# talking-train.net
KiCad netlist of a schematic drawn in EasyEDA Pro
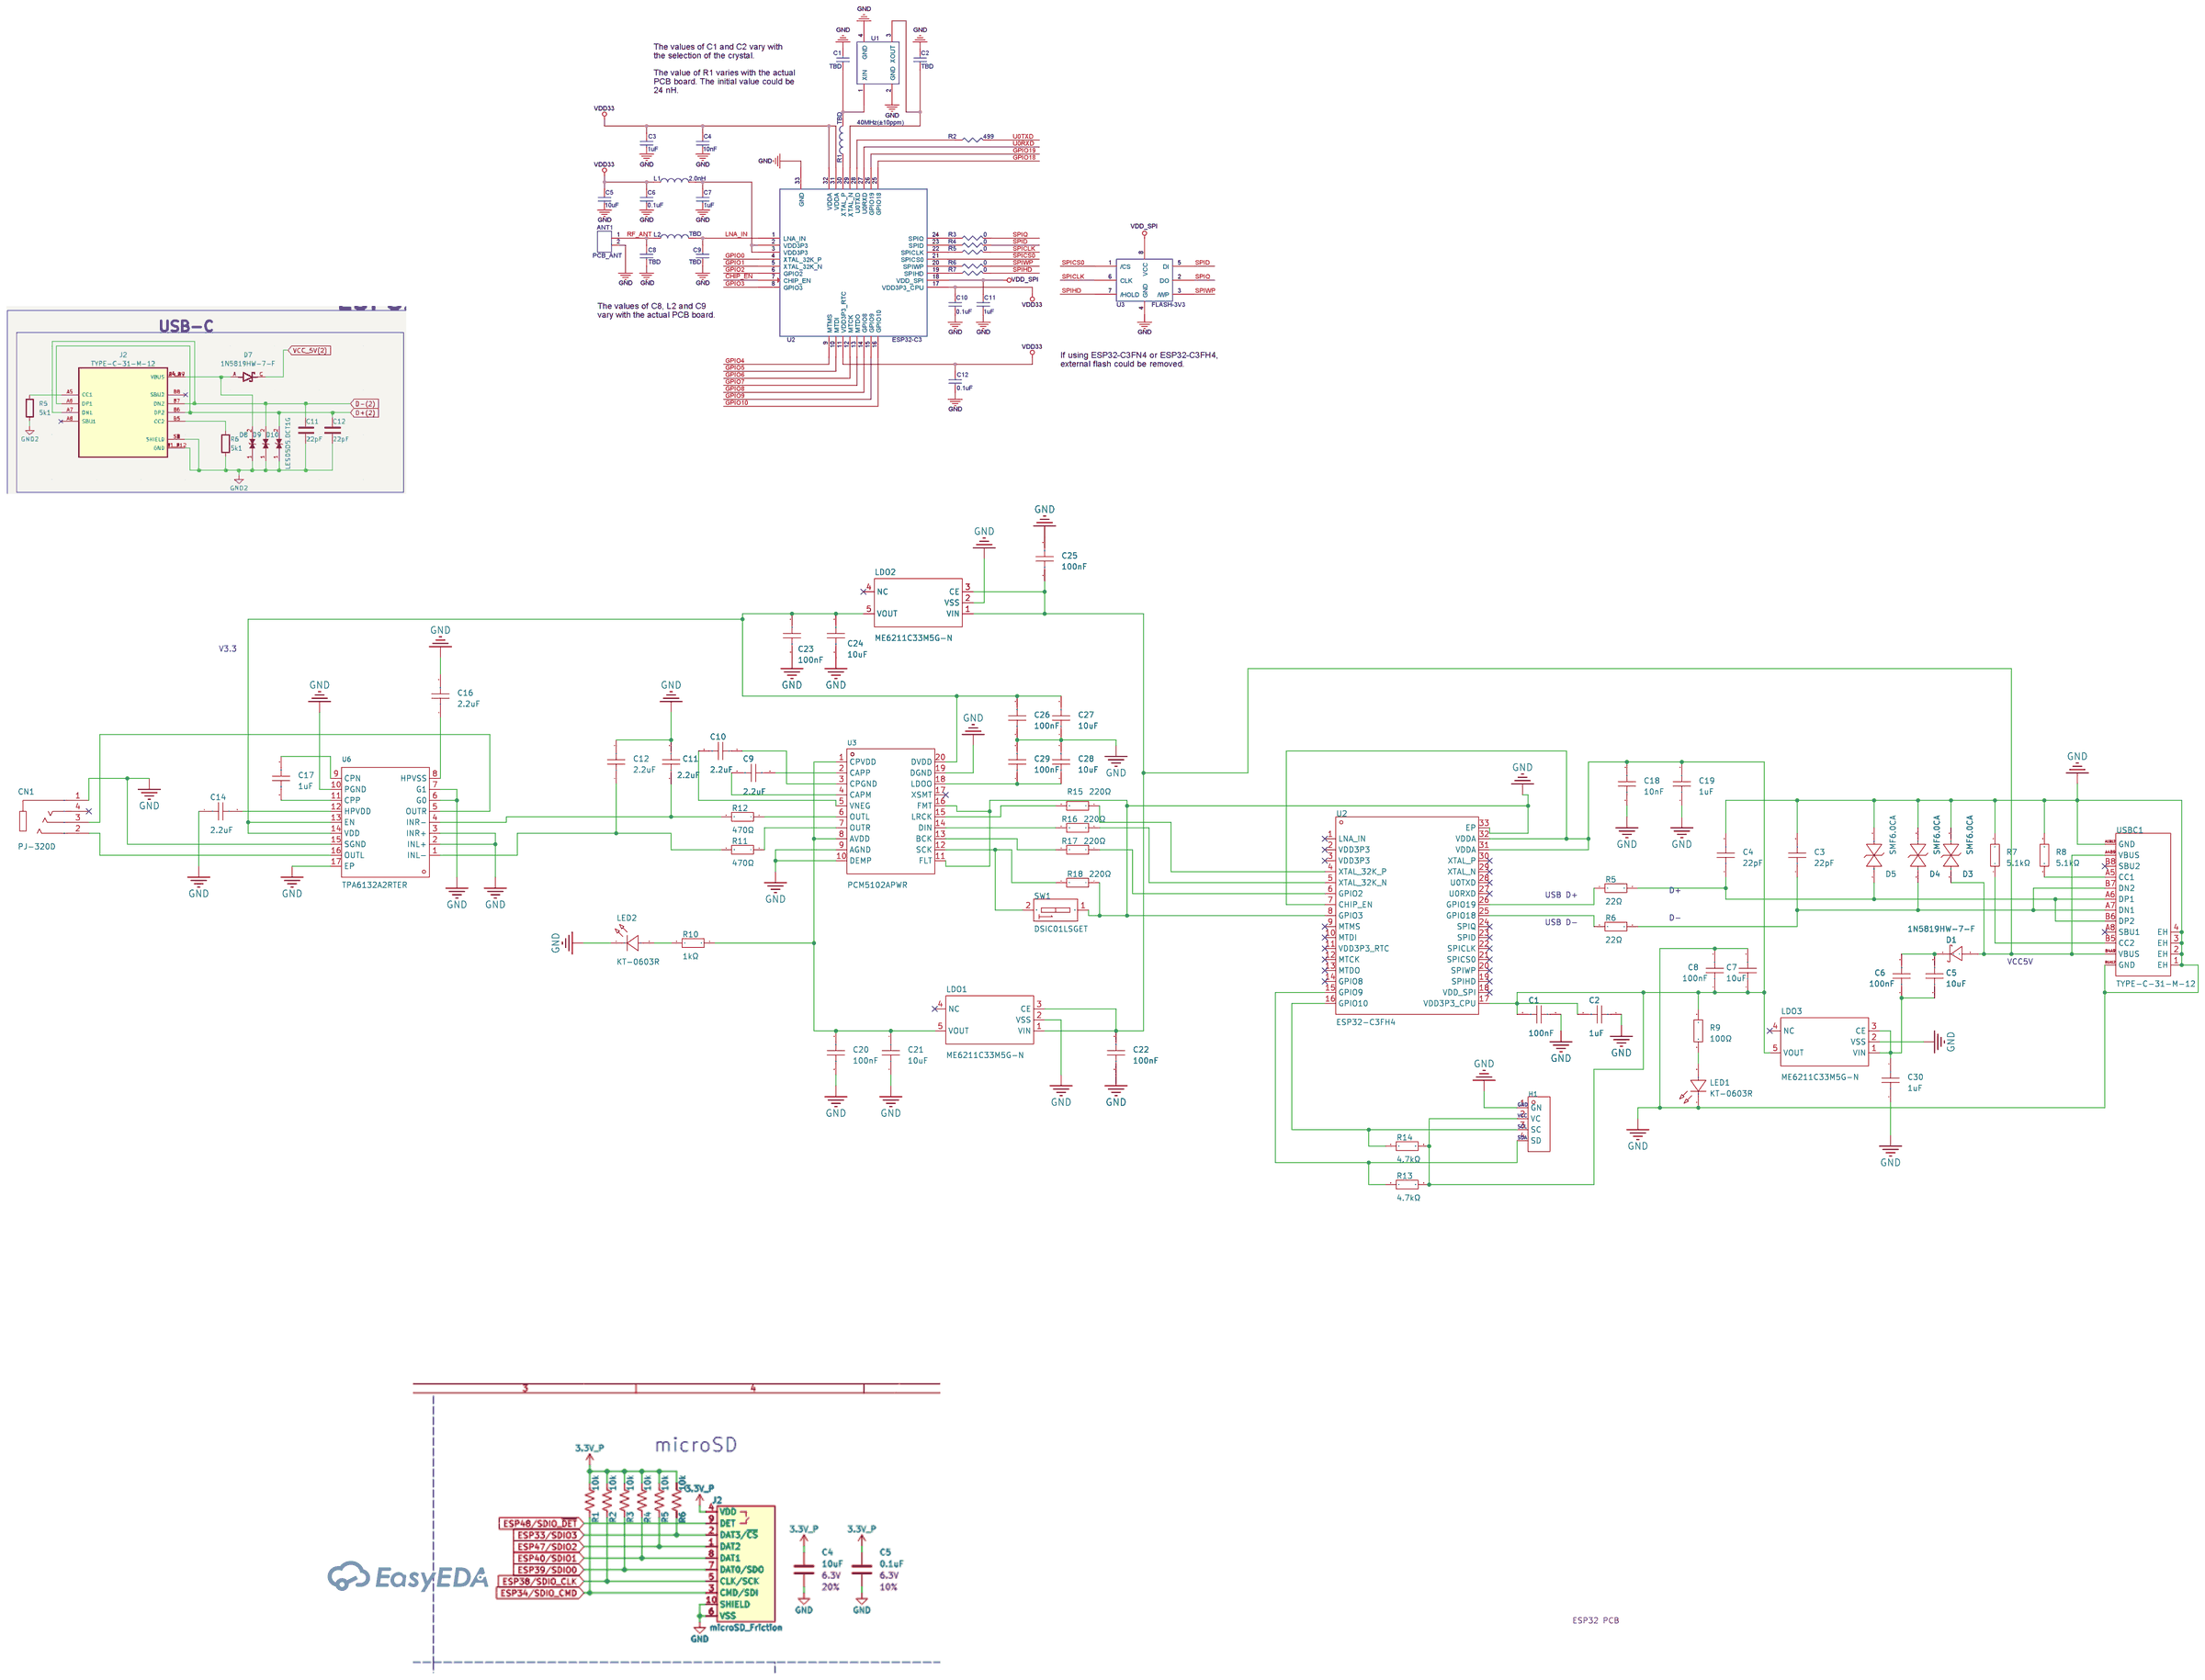
[diagram p0: schematic sheet]

(export (version "E")
  (design (tool "Eeschema 10.0.6"))
  (components
    (comp (ref "C1")
      (value "100nF")
      (footprint "easyedapro:C0603")
      (description "Capacitance:100nF Tolerance:±10% Tolerance:±10% Voltage Rating:50V Temperature Coefficient:X7R")
      (fields
        (field (name "Manufacturer Part") "CC0603KRX7R9BB104")
        (field (name "Manufacturer") "YAGEO(国巨)")
      )
      (libsource (lib "easyedapro") (part "CAP"))
    )
    (comp (ref "C2")
      (value "1uF")
      (footprint "easyedapro:C0603")
      (description "Capacitance:1uF Tolerance:±10% Tolerance:±10% Voltage Rating:50V Temperature Coefficient:X5R")
      (fields
        (field (name "Manufacturer Part") "CL10A105KB8NNNC")
        (field (name "Manufacturer") "SAMSUNG(三星)")
      )
      (libsource (lib "easyedapro") (part "CAP"))
    )
    (comp (ref "C3")
      (value "22pF")
      (footprint "easyedapro:C0603")
      (description "Capacitance:22pF Tolerance:±5% Tolerance:±5% Voltage Rating:50V Temperature Coefficient:C0G")
      (fields
        (field (name "Manufacturer Part") "CL10C220JB8NNNC")
        (field (name "Manufacturer") "SAMSUNG(三星)")
      )
      (libsource (lib "easyedapro") (part "CAP"))
    )
    (comp (ref "C4")
      (value "22pF")
      (footprint "easyedapro:C0603")
      (description "Capacitance:22pF Tolerance:±5% Tolerance:±5% Voltage Rating:50V Temperature Coefficient:C0G")
      (fields
        (field (name "Manufacturer Part") "CL10C220JB8NNNC")
        (field (name "Manufacturer") "SAMSUNG(三星)")
      )
      (libsource (lib "easyedapro") (part "CAP"))
    )
    (comp (ref "C5")
      (value "10uF")
      (footprint "easyedapro:C0603")
      (description "Capacitance:10uF Tolerance:±10% Tolerance:±10% Voltage Rating:10V Temperature Coefficient:X5R")
      (fields
        (field (name "Manufacturer Part") "CL10A106KP8NNNC")
        (field (name "Manufacturer") "SAMSUNG(三星)")
      )
      (libsource (lib "easyedapro") (part "CAP"))
    )
    (comp (ref "C6")
      (value "100nF")
      (footprint "easyedapro:C0603")
      (description "Capacitance:100nF Tolerance:±10% Tolerance:±10% Voltage Rating:50V Temperature Coefficient:X7R")
      (fields
        (field (name "Manufacturer Part") "CC0603KRX7R9BB104")
        (field (name "Manufacturer") "YAGEO(国巨)")
      )
      (libsource (lib "easyedapro") (part "CAP"))
    )
    (comp (ref "C7")
      (value "10uF")
      (footprint "easyedapro:C0603")
      (description "Capacitance:10uF Tolerance:±10% Tolerance:±10% Voltage Rating:10V Temperature Coefficient:X5R")
      (fields
        (field (name "Manufacturer Part") "CL10A106KP8NNNC")
        (field (name "Manufacturer") "SAMSUNG(三星)")
      )
      (libsource (lib "easyedapro") (part "CAP"))
    )
    (comp (ref "C8")
      (value "100nF")
      (footprint "easyedapro:C0603")
      (description "Capacitance:100nF Tolerance:±10% Tolerance:±10% Voltage Rating:50V Temperature Coefficient:X7R")
      (fields
        (field (name "Manufacturer Part") "CC0603KRX7R9BB104")
        (field (name "Manufacturer") "YAGEO(国巨)")
      )
      (libsource (lib "easyedapro") (part "CAP"))
    )
    (comp (ref "C9")
      (value "2.2uF")
      (footprint "easyedapro:C0603")
      (description "Capacitance:2.2uF Tolerance:±10% Tolerance:±10% Voltage Rating:16V Temperature Coefficient:X5R")
      (fields
        (field (name "Manufacturer Part") "CL10A225KO8NNNC")
        (field (name "Manufacturer") "SAMSUNG(三星)")
      )
      (libsource (lib "easyedapro") (part "CAP"))
    )
    (comp (ref "C10")
      (value "2.2uF")
      (footprint "easyedapro:C0603")
      (description "Capacitance:2.2uF Tolerance:±10% Tolerance:±10% Voltage Rating:16V Temperature Coefficient:X5R")
      (fields
        (field (name "Manufacturer Part") "CL10A225KO8NNNC")
        (field (name "Manufacturer") "SAMSUNG(三星)")
      )
      (libsource (lib "easyedapro") (part "CAP"))
    )
    (comp (ref "C11")
      (value "2.2uF")
      (footprint "easyedapro:C0603")
      (description "Capacitance:2.2uF Tolerance:±10% Tolerance:±10% Voltage Rating:16V Temperature Coefficient:X5R")
      (fields
        (field (name "Manufacturer Part") "CL10A225KO8NNNC")
        (field (name "Manufacturer") "SAMSUNG(三星)")
      )
      (libsource (lib "easyedapro") (part "CAP"))
    )
    (comp (ref "C12")
      (value "2.2uF")
      (footprint "easyedapro:C0603")
      (description "Capacitance:2.2uF Tolerance:±10% Tolerance:±10% Voltage Rating:16V Temperature Coefficient:X5R")
      (fields
        (field (name "Manufacturer Part") "CL10A225KO8NNNC")
        (field (name "Manufacturer") "SAMSUNG(三星)")
      )
      (libsource (lib "easyedapro") (part "CAP"))
    )
    (comp (ref "C14")
      (value "2.2uF")
      (footprint "easyedapro:C0603")
      (description "Capacitance:2.2uF Tolerance:±10% Tolerance:±10% Voltage Rating:16V Temperature Coefficient:X5R")
      (fields
        (field (name "Manufacturer Part") "CL10A225KO8NNNC")
        (field (name "Manufacturer") "SAMSUNG(三星)")
      )
      (libsource (lib "easyedapro") (part "CAP"))
    )
    (comp (ref "C16")
      (value "2.2uF")
      (footprint "easyedapro:C0603")
      (description "Capacitance:2.2uF Tolerance:±10% Tolerance:±10% Voltage Rating:16V Temperature Coefficient:X5R")
      (fields
        (field (name "Manufacturer Part") "CL10A225KO8NNNC")
        (field (name "Manufacturer") "SAMSUNG(三星)")
      )
      (libsource (lib "easyedapro") (part "CAP"))
    )
    (comp (ref "C17")
      (value "1uF")
      (footprint "easyedapro:C0603")
      (description "Capacitance:1uF Tolerance:±10% Tolerance:±10% Voltage Rating:50V Temperature Coefficient:X5R")
      (fields
        (field (name "Manufacturer Part") "CL10A105KB8NNNC")
        (field (name "Manufacturer") "SAMSUNG(三星)")
      )
      (libsource (lib "easyedapro") (part "CAP"))
    )
    (comp (ref "C18")
      (value "10nF")
      (footprint "easyedapro:C0603")
      (description "Capacitance:10nF Tolerance:±10% Tolerance:±10% Voltage Rating:50V Temperature Coefficient:X7R")
      (fields (field (name "Manufacturer Part") "0603B103K500NT") (field (name "Manufacturer") "FH(风华)"))
      (libsource (lib "easyedapro") (part "CAP"))
    )
    (comp (ref "C19")
      (value "1uF")
      (footprint "easyedapro:C0603")
      (description "Capacitance:1uF Tolerance:±10% Tolerance:±10% Voltage Rating:50V Temperature Coefficient:X5R")
      (fields
        (field (name "Manufacturer Part") "CL10A105KB8NNNC")
        (field (name "Manufacturer") "SAMSUNG(三星)")
      )
      (libsource (lib "easyedapro") (part "CAP"))
    )
    (comp (ref "C20")
      (value "100nF")
      (footprint "easyedapro:C0603")
      (description "Capacitance:100nF Tolerance:±10% Tolerance:±10% Voltage Rating:50V Temperature Coefficient:X7R")
      (fields
        (field (name "Manufacturer Part") "CC0603KRX7R9BB104")
        (field (name "Manufacturer") "YAGEO(国巨)")
      )
      (libsource (lib "easyedapro") (part "CAP"))
    )
    (comp (ref "C21")
      (value "10uF")
      (footprint "easyedapro:C0603")
      (description "Capacitance:10uF Tolerance:±10% Tolerance:±10% Voltage Rating:10V Temperature Coefficient:X5R")
      (fields
        (field (name "Manufacturer Part") "CL10A106KP8NNNC")
        (field (name "Manufacturer") "SAMSUNG(三星)")
      )
      (libsource (lib "easyedapro") (part "CAP"))
    )
    (comp (ref "C22")
      (value "100nF")
      (footprint "easyedapro:C0603")
      (description "Capacitance:100nF Tolerance:±10% Tolerance:±10% Voltage Rating:50V Temperature Coefficient:X7R")
      (fields
        (field (name "Manufacturer Part") "CC0603KRX7R9BB104")
        (field (name "Manufacturer") "YAGEO(国巨)")
      )
      (libsource (lib "easyedapro") (part "CAP"))
    )
    (comp (ref "C23")
      (value "100nF")
      (footprint "easyedapro:C0603")
      (description "Capacitance:100nF Tolerance:±10% Tolerance:±10% Voltage Rating:50V Temperature Coefficient:X7R")
      (fields
        (field (name "Manufacturer Part") "CC0603KRX7R9BB104")
        (field (name "Manufacturer") "YAGEO(国巨)")
      )
      (libsource (lib "easyedapro") (part "CAP"))
    )
    (comp (ref "C24")
      (value "10uF")
      (footprint "easyedapro:C0603")
      (description "Capacitance:10uF Tolerance:±10% Tolerance:±10% Voltage Rating:10V Temperature Coefficient:X5R")
      (fields
        (field (name "Manufacturer Part") "CL10A106KP8NNNC")
        (field (name "Manufacturer") "SAMSUNG(三星)")
      )
      (libsource (lib "easyedapro") (part "CAP"))
    )
    (comp (ref "C25")
      (value "100nF")
      (footprint "easyedapro:C0603")
      (description "Capacitance:100nF Tolerance:±10% Tolerance:±10% Voltage Rating:50V Temperature Coefficient:X7R")
      (fields
        (field (name "Manufacturer Part") "CC0603KRX7R9BB104")
        (field (name "Manufacturer") "YAGEO(国巨)")
      )
      (libsource (lib "easyedapro") (part "CAP"))
    )
    (comp (ref "C26")
      (value "100nF")
      (footprint "easyedapro:C0603")
      (description "Capacitance:100nF Tolerance:±10% Tolerance:±10% Voltage Rating:50V Temperature Coefficient:X7R")
      (fields
        (field (name "Manufacturer Part") "CC0603KRX7R9BB104")
        (field (name "Manufacturer") "YAGEO(国巨)")
      )
      (libsource (lib "easyedapro") (part "CAP"))
    )
    (comp (ref "C27")
      (value "10uF")
      (footprint "easyedapro:C0603")
      (description "Capacitance:10uF Tolerance:±10% Tolerance:±10% Voltage Rating:10V Temperature Coefficient:X5R")
      (fields
        (field (name "Manufacturer Part") "CL10A106KP8NNNC")
        (field (name "Manufacturer") "SAMSUNG(三星)")
      )
      (libsource (lib "easyedapro") (part "CAP"))
    )
    (comp (ref "C28")
      (value "10uF")
      (footprint "easyedapro:C0603")
      (description "Capacitance:10uF Tolerance:±10% Tolerance:±10% Voltage Rating:10V Temperature Coefficient:X5R")
      (fields
        (field (name "Manufacturer Part") "CL10A106KP8NNNC")
        (field (name "Manufacturer") "SAMSUNG(三星)")
      )
      (libsource (lib "easyedapro") (part "CAP"))
    )
    (comp (ref "C29")
      (value "100nF")
      (footprint "easyedapro:C0603")
      (description "Capacitance:100nF Tolerance:±10% Tolerance:±10% Voltage Rating:50V Temperature Coefficient:X7R")
      (fields
        (field (name "Manufacturer Part") "CC0603KRX7R9BB104")
        (field (name "Manufacturer") "YAGEO(国巨)")
      )
      (libsource (lib "easyedapro") (part "CAP"))
    )
    (comp (ref "C30")
      (value "1uF")
      (footprint "easyedapro:C0603")
      (description "Capacitance:1uF Tolerance:±10% Tolerance:±10% Voltage Rating:50V Temperature Coefficient:X7R")
      (fields
        (field (name "Manufacturer Part") "CL31B105KBHNNNE")
        (field (name "Manufacturer") "SAMSUNG(三星)")
      )
      (libsource (lib "easyedapro") (part "CAP"))
    )
    (comp (ref "CN1")
      (value "PJ-320D")
      (footprint "easyedapro:AUDIO-SMD_PJ-320D-1")
      (fields (field (name "Manufacturer") "SHOU HAN(首韩)"))
      (libsource (lib "easyedapro") (part "PJ-320D"))
    )
    (comp (ref "D1")
      (value "1N5819HW-7-F")
      (footprint "easyedapro:SOD-123_L2.7-W1.6-LS3.7-RD")
      (fields (field (name "Manufacturer") "DIODES(美台)"))
      (libsource (lib "easyedapro") (part "1N5819HW-7-F"))
    )
    (comp (ref "D3")
      (value "SMF6.0CA")
      (footprint "easyedapro:SOD-123FL_L2.7-W1.8-LS3.8-BI")
      (fields (field (name "Manufacturer") "R+O(宏嘉诚)"))
      (libsource (lib "easyedapro") (part "SMF6.0CA_C19077500"))
    )
    (comp (ref "D4")
      (value "SMF6.0CA")
      (footprint "easyedapro:SOD-123FL_L2.7-W1.8-LS3.8-BI")
      (fields (field (name "Manufacturer") "R+O(宏嘉诚)"))
      (libsource (lib "easyedapro") (part "SMF6.0CA_C19077500"))
    )
    (comp (ref "D5")
      (value "SMF6.0CA")
      (footprint "easyedapro:SOD-123FL_L2.7-W1.8-LS3.8-BI")
      (fields (field (name "Manufacturer") "R+O(宏嘉诚)"))
      (libsource (lib "easyedapro") (part "SMF6.0CA_C19077500"))
    )
    (comp (ref "H1")
      (value "2.54-1*4P母")
      (footprint "easyedapro:HDR-TH_4P-P2.54-V-F")
      (fields (field (name "Manufacturer") "BOOMELE(博穆精密)"))
      (libsource (lib "easyedapro") (part "2.54-1*4P母"))
    )
    (comp (ref "LDO1")
      (value "ME6211C33M5G-N")
      (footprint "easyedapro:SOT-23-5_L3.0-W1.7-P0.95-LS2.8-BL")
      (fields (field (name "Manufacturer") "MICRONE(南京微盟)"))
      (libsource (lib "easyedapro") (part "ME6211C33M5G-N"))
    )
    (comp (ref "LDO2")
      (value "ME6211C33M5G-N")
      (footprint "easyedapro:SOT-23-5_L3.0-W1.7-P0.95-LS2.8-BL")
      (fields (field (name "Manufacturer") "MICRONE(南京微盟)"))
      (libsource (lib "easyedapro") (part "ME6211C33M5G-N"))
    )
    (comp (ref "LDO3")
      (value "ME6211C33M5G-N")
      (footprint "easyedapro:SOT-23-5_L3.0-W1.7-P0.95-LS2.8-BL")
      (fields (field (name "Manufacturer") "MICRONE(南京微盟)"))
      (libsource (lib "easyedapro") (part "ME6211C33M5G-N"))
    )
    (comp (ref "LED1")
      (value "KT-0603R")
      (footprint "easyedapro:LED0603-RD_RED")
      (fields (field (name "Manufacturer") "KENTO"))
      (libsource (lib "easyedapro") (part "XL-1608SURC-06"))
    )
    (comp (ref "LED2")
      (value "KT-0603R")
      (footprint "easyedapro:LED0603-RD_RED")
      (fields (field (name "Manufacturer") "KENTO"))
      (libsource (lib "easyedapro") (part "XL-1608SURC-06"))
    )
    (comp (ref "R5")
      (value "22Ω")
      (footprint "easyedapro:R0603")
      (fields
        (field (name "Manufacturer Part") "0603WAF220JT5E")
        (field (name "Manufacturer") "UNI-ROYAL(厚声)")
      )
      (libsource (lib "easyedapro") (part "Res"))
    )
    (comp (ref "R6")
      (value "22Ω")
      (footprint "easyedapro:R0603")
      (fields
        (field (name "Manufacturer Part") "0603WAF220JT5E")
        (field (name "Manufacturer") "UNI-ROYAL(厚声)")
      )
      (libsource (lib "easyedapro") (part "Res"))
    )
    (comp (ref "R7")
      (value "5.1kΩ")
      (footprint "easyedapro:R0603")
      (fields
        (field (name "Manufacturer Part") "0805W8F5101T5E")
        (field (name "Manufacturer") "UNI-ROYAL(厚声)")
      )
      (libsource (lib "easyedapro") (part "Res"))
    )
    (comp (ref "R8")
      (value "5.1kΩ")
      (footprint "easyedapro:R0603")
      (fields
        (field (name "Manufacturer Part") "0805W8F5101T5E")
        (field (name "Manufacturer") "UNI-ROYAL(厚声)")
      )
      (libsource (lib "easyedapro") (part "Res"))
    )
    (comp (ref "R9")
      (value "100Ω")
      (footprint "easyedapro:R0603")
      (fields
        (field (name "Manufacturer Part") "0603WAF1000T5E")
        (field (name "Manufacturer") "UNI-ROYAL(厚声)")
      )
      (libsource (lib "easyedapro") (part "Res"))
    )
    (comp (ref "R10")
      (value "1kΩ")
      (footprint "easyedapro:R0603")
      (fields
        (field (name "Manufacturer Part") "0603WAF1001T5E")
        (field (name "Manufacturer") "UNI-ROYAL(厚声)")
      )
      (libsource (lib "easyedapro") (part "Res"))
    )
    (comp (ref "R11")
      (value "470Ω")
      (footprint "easyedapro:R0603")
      (fields
        (field (name "Manufacturer Part") "0603WAF4700T5E")
        (field (name "Manufacturer") "UNI-ROYAL(厚声)")
      )
      (libsource (lib "easyedapro") (part "Res"))
    )
    (comp (ref "R12")
      (value "470Ω")
      (footprint "easyedapro:R0603")
      (fields
        (field (name "Manufacturer Part") "0603WAF4700T5E")
        (field (name "Manufacturer") "UNI-ROYAL(厚声)")
      )
      (libsource (lib "easyedapro") (part "Res"))
    )
    (comp (ref "R13")
      (value "4.7kΩ")
      (footprint "easyedapro:R0603")
      (fields
        (field (name "Manufacturer Part") "0603WAF4701T5E")
        (field (name "Manufacturer") "UNI-ROYAL(厚声)")
      )
      (libsource (lib "easyedapro") (part "Res"))
    )
    (comp (ref "R14")
      (value "4.7kΩ")
      (footprint "easyedapro:R0603")
      (fields
        (field (name "Manufacturer Part") "0603WAF4701T5E")
        (field (name "Manufacturer") "UNI-ROYAL(厚声)")
      )
      (libsource (lib "easyedapro") (part "Res"))
    )
    (comp (ref "R15")
      (value "220Ω")
      (footprint "easyedapro:R0603")
      (fields
        (field (name "Manufacturer Part") "0603WAF2200T5E")
        (field (name "Manufacturer") "UNI-ROYAL(厚声)")
      )
      (libsource (lib "easyedapro") (part "Res"))
    )
    (comp (ref "R16")
      (value "220Ω")
      (footprint "easyedapro:R0603")
      (fields
        (field (name "Manufacturer Part") "0603WAF2200T5E")
        (field (name "Manufacturer") "UNI-ROYAL(厚声)")
      )
      (libsource (lib "easyedapro") (part "Res"))
    )
    (comp (ref "R17")
      (value "220Ω")
      (footprint "easyedapro:R0603")
      (fields
        (field (name "Manufacturer Part") "0603WAF2200T5E")
        (field (name "Manufacturer") "UNI-ROYAL(厚声)")
      )
      (libsource (lib "easyedapro") (part "Res"))
    )
    (comp (ref "R18")
      (value "220Ω")
      (footprint "easyedapro:R0603")
      (fields
        (field (name "Manufacturer Part") "0603WAF2200T5E")
        (field (name "Manufacturer") "UNI-ROYAL(厚声)")
      )
      (libsource (lib "easyedapro") (part "Res"))
    )
    (comp (ref "SW1")
      (value "DSIC01LSGET")
      (footprint "easyedapro:SW-SMD_DSIC01LSGET")
      (description "Type:Slide, Rocked Circuit:SPST Number of Positions:1 Lead Pitch:- Operating Life:- Color:Black")
      (fields (field (name "Manufacturer") "YE"))
      (libsource (lib "easyedapro") (part "DSIC01LSGET"))
    )
    (comp (ref "U2")
      (value "ESP32-C3FH4")
      (footprint "easyedapro:QFN-32_L5.0-W5.0-P0.50-TL-EP3.7")
      (fields (field (name "Manufacturer") "ESPRESSIF(乐鑫)"))
      (libsource (lib "easyedapro") (part "ESP32-C3FH4"))
    )
    (comp (ref "U3")
      (value "PCM5102APWR")
      (footprint "easyedapro:TSSOP-20_L6.5-W4.4-P0.65-LS6.4-BL")
      (fields (field (name "Manufacturer") "TI(德州仪器)"))
      (libsource (lib "easyedapro") (part "PCM5102APWR"))
    )
    (comp (ref "U6")
      (value "TPA6132A2RTER")
      (footprint "easyedapro:WQFN-16_L3.0-W3.0-P0.50-TL-EP1.6")
      (fields (field (name "Manufacturer") "TI(德州仪器)"))
      (libsource (lib "easyedapro") (part "TPA6132A2RTER"))
    )
    (comp (ref "USBC1")
      (value "TYPE-C-31-M-12")
      (footprint "easyedapro:USB-C_SMD-TYPE-C-31-M-12_1")
      (fields (field (name "Manufacturer") "韩国韩荣"))
      (libsource (lib "easyedapro") (part "TYPE-C-31-M-12"))
    )
  )
  (nets
    (net (code "1") (name "GND") (class "Default")
      (node (ref "C1") (pin "1") (pinfunction "1_1") (pintype "input"))
      (node (ref "C11") (pin "2") (pinfunction "2_2") (pintype "input"))
      (node (ref "C12") (pin "2") (pinfunction "2_2") (pintype "input"))
      (node (ref "C14") (pin "1") (pinfunction "1_1") (pintype "input"))
      (node (ref "C16") (pin "2") (pinfunction "2_2") (pintype "input"))
      (node (ref "C18") (pin "1") (pinfunction "1_1") (pintype "input"))
      (node (ref "C19") (pin "1") (pinfunction "1_1") (pintype "input"))
      (node (ref "C2") (pin "1") (pinfunction "1_1") (pintype "input"))
      (node (ref "C20") (pin "2") (pinfunction "2_2") (pintype "input"))
      (node (ref "C21") (pin "2") (pinfunction "2_2") (pintype "input"))
      (node (ref "C22") (pin "2") (pinfunction "2_2") (pintype "input"))
      (node (ref "C23") (pin "2") (pinfunction "2_2") (pintype "input"))
      (node (ref "C24") (pin "2") (pinfunction "2_2") (pintype "input"))
      (node (ref "C25") (pin "2") (pinfunction "2_2") (pintype "input"))
      (node (ref "C26") (pin "1") (pinfunction "1_1") (pintype "input"))
      (node (ref "C27") (pin "1") (pinfunction "1_1") (pintype "input"))
      (node (ref "C28") (pin "2") (pinfunction "2_2") (pintype "input"))
      (node (ref "C29") (pin "2") (pinfunction "2_2") (pintype "input"))
      (node (ref "C3") (pin "2") (pinfunction "2_2") (pintype "input"))
      (node (ref "C30") (pin "2") (pinfunction "2_2") (pintype "input"))
      (node (ref "C4") (pin "2") (pinfunction "2_2") (pintype "input"))
      (node (ref "C7") (pin "2") (pinfunction "2_2") (pintype "input"))
      (node (ref "C8") (pin "2") (pinfunction "2_2") (pintype "input"))
      (node (ref "CN1") (pin "1") (pinfunction "1_1") (pintype "unspecified"))
      (node (ref "D3") (pin "1") (pinfunction "1_1") (pintype "unspecified"))
      (node (ref "D4") (pin "1") (pinfunction "1_1") (pintype "unspecified"))
      (node (ref "D5") (pin "1") (pinfunction "1_1") (pintype "unspecified"))
      (node (ref "H1") (pin "1") (pinfunction "GN_1") (pintype "input"))
      (node (ref "LDO1") (pin "2") (pinfunction "VSS_2") (pintype "unspecified"))
      (node (ref "LDO2") (pin "2") (pinfunction "VSS_2") (pintype "unspecified"))
      (node (ref "LDO3") (pin "2") (pinfunction "VSS_2") (pintype "unspecified"))
      (node (ref "LED1") (pin "1") (pinfunction "K_1") (pintype "unspecified"))
      (node (ref "LED2") (pin "1") (pinfunction "K_1") (pintype "unspecified"))
      (node (ref "R18") (pin "1") (pinfunction "1_1") (pintype "input"))
      (node (ref "R7") (pin "2") (pinfunction "2_2") (pintype "input"))
      (node (ref "R8") (pin "2") (pinfunction "2_2") (pintype "input"))
      (node (ref "SW1") (pin "1") (pinfunction "A1_1") (pintype "input"))
      (node (ref "U2") (pin "33") (pinfunction "EP_33") (pintype "unspecified"))
      (node (ref "U2") (pin "8") (pinfunction "GPIO3_8") (pintype "unspecified"))
      (node (ref "U3") (pin "10") (pinfunction "DEMP_10") (pintype "input"))
      (node (ref "U3") (pin "11") (pinfunction "FLT_11") (pintype "input"))
      (node (ref "U3") (pin "16") (pinfunction "FMT_16") (pintype "input"))
      (node (ref "U3") (pin "19") (pinfunction "DGND_19") (pintype "input"))
      (node (ref "U3") (pin "9") (pinfunction "AGND_9") (pintype "input"))
      (node (ref "U6") (pin "10") (pinfunction "PGND_10") (pintype "input"))
      (node (ref "U6") (pin "15") (pinfunction "SGND_15") (pintype "input"))
      (node (ref "U6") (pin "17") (pinfunction "EP_17") (pintype "input"))
      (node (ref "U6") (pin "2") (pinfunction "INL+_2") (pintype "input"))
      (node (ref "U6") (pin "3") (pinfunction "INR+_3") (pintype "input"))
      (node (ref "U6") (pin "6") (pinfunction "G0_6") (pintype "input"))
      (node (ref "U6") (pin "7") (pinfunction "G1_7") (pintype "input"))
      (node (ref "USBC1") (pin "1") (pinfunction "EH_1") (pintype "unspecified"))
      (node (ref "USBC1") (pin "2") (pinfunction "EH_2") (pintype "unspecified"))
      (node (ref "USBC1") (pin "3") (pinfunction "EH_3") (pintype "unspecified"))
      (node (ref "USBC1") (pin "4") (pinfunction "EH_4") (pintype "unspecified"))
      (node (ref "USBC1") (pin "A1B12") (pinfunction "GND_A1B12") (pintype "unspecified"))
      (node (ref "USBC1") (pin "B1A12") (pinfunction "GND_B1A12") (pintype "unspecified"))
    )
    (net (code "2") (name "Net-(D1-A)") (class "Default")
      (node (ref "C22") (pin "1") (pinfunction "1_1") (pintype "input"))
      (node (ref "C25") (pin "1") (pinfunction "1_1") (pintype "input"))
      (node (ref "D1") (pin "2") (pinfunction "A_2") (pintype "unspecified"))
      (node (ref "D3") (pin "2") (pinfunction "2_2") (pintype "unspecified"))
      (node (ref "LDO1") (pin "1") (pinfunction "VIN_1") (pintype "unspecified"))
      (node (ref "LDO1") (pin "3") (pinfunction "CE_3") (pintype "unspecified"))
      (node (ref "LDO2") (pin "1") (pinfunction "VIN_1") (pintype "unspecified"))
      (node (ref "LDO2") (pin "3") (pinfunction "CE_3") (pintype "unspecified"))
      (node (ref "USBC1") (pin "A4B9") (pinfunction "VBUS_A4B9") (pintype "unspecified"))
      (node (ref "USBC1") (pin "B4A9") (pinfunction "VBUS_B4A9") (pintype "unspecified"))
    )
    (net (code "3") (name "Net-(D1-K)") (class "Default")
      (node (ref "C5") (pin "2") (pinfunction "2_2") (pintype "input"))
      (node (ref "C6") (pin "2") (pinfunction "2_2") (pintype "input"))
      (node (ref "D1") (pin "1") (pinfunction "K_1") (pintype "unspecified"))
    )
    (net (code "4") (name "Net-(H1-SC)") (class "Default")
      (node (ref "H1") (pin "3") (pinfunction "SC_3") (pintype "input"))
      (node (ref "R14") (pin "1") (pinfunction "1_1") (pintype "input"))
      (node (ref "U2") (pin "16") (pinfunction "GPIO10_16") (pintype "unspecified"))
    )
    (net (code "5") (name "Net-(H1-SD)") (class "Default")
      (node (ref "H1") (pin "4") (pinfunction "SD_4") (pintype "input"))
      (node (ref "R13") (pin "1") (pinfunction "1_1") (pintype "input"))
      (node (ref "U2") (pin "15") (pinfunction "GPIO9_15") (pintype "unspecified"))
    )
    (net (code "6") (name "Net-(H1-VC)") (class "Default")
      (node (ref "C1") (pin "2") (pinfunction "2_2") (pintype "input"))
      (node (ref "C18") (pin "2") (pinfunction "2_2") (pintype "input"))
      (node (ref "C19") (pin "2") (pinfunction "2_2") (pintype "input"))
      (node (ref "C2") (pin "2") (pinfunction "2_2") (pintype "input"))
      (node (ref "C7") (pin "1") (pinfunction "1_1") (pintype "input"))
      (node (ref "C8") (pin "1") (pinfunction "1_1") (pintype "input"))
      (node (ref "H1") (pin "2") (pinfunction "VC_2") (pintype "input"))
      (node (ref "LDO3") (pin "5") (pinfunction "VOUT_5") (pintype "unspecified"))
      (node (ref "R13") (pin "2") (pinfunction "2_2") (pintype "input"))
      (node (ref "R14") (pin "2") (pinfunction "2_2") (pintype "input"))
      (node (ref "R9") (pin "2") (pinfunction "2_2") (pintype "input"))
      (node (ref "U2") (pin "17") (pinfunction "VDD3P3_CPU_17") (pintype "unspecified"))
      (node (ref "U2") (pin "31") (pinfunction "VDDA_31") (pintype "unspecified"))
      (node (ref "U2") (pin "32") (pinfunction "VDDA_32") (pintype "unspecified"))
      (node (ref "U2") (pin "7") (pinfunction "CHIP_EN_7") (pintype "unspecified"))
    )
    (net (code "7") (name "Net-(LDO1-VOUT)") (class "Default")
      (node (ref "C20") (pin "1") (pinfunction "1_1") (pintype "input"))
      (node (ref "C21") (pin "1") (pinfunction "1_1") (pintype "input"))
      (node (ref "LDO1") (pin "5") (pinfunction "VOUT_5") (pintype "unspecified"))
      (node (ref "R10") (pin "1") (pinfunction "1_1") (pintype "input"))
      (node (ref "U3") (pin "1") (pinfunction "CPVDD_1") (pintype "input"))
      (node (ref "U3") (pin "8") (pinfunction "AVDD_8") (pintype "input"))
    )
    (net (code "8") (name "Net-(LDO2-VOUT)") (class "Default")
      (node (ref "C23") (pin "1") (pinfunction "1_1") (pintype "input"))
      (node (ref "C24") (pin "1") (pinfunction "1_1") (pintype "input"))
      (node (ref "C26") (pin "2") (pinfunction "2_2") (pintype "input"))
      (node (ref "C27") (pin "2") (pinfunction "2_2") (pintype "input"))
      (node (ref "LDO2") (pin "5") (pinfunction "VOUT_5") (pintype "unspecified"))
      (node (ref "U3") (pin "20") (pinfunction "DVDD_20") (pintype "input"))
      (node (ref "U6") (pin "13") (pinfunction "EN_13") (pintype "input"))
      (node (ref "U6") (pin "14") (pinfunction "VDD_14") (pintype "input"))
    )
    (net (code "9") (name "Net-(LDO3-CE)") (class "Default")
      (node (ref "C30") (pin "1") (pinfunction "1_1") (pintype "input"))
      (node (ref "C5") (pin "1") (pinfunction "1_1") (pintype "input"))
      (node (ref "C6") (pin "1") (pinfunction "1_1") (pintype "input"))
      (node (ref "LDO3") (pin "1") (pinfunction "VIN_1") (pintype "unspecified"))
      (node (ref "LDO3") (pin "3") (pinfunction "CE_3") (pintype "unspecified"))
    )
    (net (code "10") (name "Net-(LED1-A)") (class "Default")
      (node (ref "LED1") (pin "2") (pinfunction "A_2") (pintype "unspecified"))
      (node (ref "R9") (pin "1") (pinfunction "1_1") (pintype "input"))
    )
    (net (code "11") (name "Net-(LED2-A)") (class "Default")
      (node (ref "LED2") (pin "2") (pinfunction "A_2") (pintype "unspecified"))
      (node (ref "R10") (pin "2") (pinfunction "2_2") (pintype "input"))
    )
    (net (code "12") (name "Net-(SW1-A2)") (class "Default")
      (node (ref "R18") (pin "2") (pinfunction "2_2") (pintype "input"))
      (node (ref "SW1") (pin "2") (pinfunction "A2_2") (pintype "input"))
      (node (ref "U3") (pin "12") (pinfunction "SCK_12") (pintype "input"))
    )
    (net (code "13") (name "Net-(U2-GPIO2)") (class "Default")
      (node (ref "R17") (pin "1") (pinfunction "1_1") (pintype "input"))
      (node (ref "U2") (pin "6") (pinfunction "GPIO2_6") (pintype "unspecified"))
    )
    (net (code "14") (name "Net-(U2-GPIO18)") (class "Default")
      (node (ref "R6") (pin "1") (pinfunction "1_1") (pintype "input"))
      (node (ref "U2") (pin "25") (pinfunction "GPIO18_25") (pintype "unspecified"))
    )
    (net (code "15") (name "Net-(U2-GPIO19)") (class "Default")
      (node (ref "R5") (pin "1") (pinfunction "1_1") (pintype "input"))
      (node (ref "U2") (pin "26") (pinfunction "GPIO19_26") (pintype "unspecified"))
    )
    (net (code "16") (name "Net-(U2-XTAL_32K_N)") (class "Default")
      (node (ref "R16") (pin "1") (pinfunction "1_1") (pintype "input"))
      (node (ref "U2") (pin "5") (pinfunction "XTAL_32K_N_5") (pintype "unspecified"))
    )
    (net (code "17") (name "Net-(U2-XTAL_32K_P)") (class "Default")
      (node (ref "R15") (pin "1") (pinfunction "1_1") (pintype "input"))
      (node (ref "U2") (pin "4") (pinfunction "XTAL_32K_P_4") (pintype "unspecified"))
    )
    (net (code "18") (name "Net-(U3-BCK)") (class "Default")
      (node (ref "R17") (pin "2") (pinfunction "2_2") (pintype "input"))
      (node (ref "U3") (pin "13") (pinfunction "BCK_13") (pintype "input"))
    )
    (net (code "19") (name "Net-(U3-CAPM)") (class "Default")
      (node (ref "C9") (pin "2") (pinfunction "2_2") (pintype "input"))
      (node (ref "U3") (pin "4") (pinfunction "CAPM_4") (pintype "input"))
    )
    (net (code "20") (name "Net-(U3-CAPP)") (class "Default")
      (node (ref "C9") (pin "1") (pinfunction "1_1") (pintype "input"))
      (node (ref "U3") (pin "2") (pinfunction "CAPP_2") (pintype "input"))
    )
    (net (code "21") (name "Net-(U3-CPGND)") (class "Default")
      (node (ref "C10") (pin "1") (pinfunction "1_1") (pintype "input"))
      (node (ref "U3") (pin "3") (pinfunction "CPGND_3") (pintype "input"))
    )
    (net (code "22") (name "Net-(U3-DIN)") (class "Default")
      (node (ref "R16") (pin "2") (pinfunction "2_2") (pintype "input"))
      (node (ref "U3") (pin "14") (pinfunction "DIN_14") (pintype "input"))
    )
    (net (code "23") (name "Net-(U3-LDOO)") (class "Default")
      (node (ref "C28") (pin "1") (pinfunction "1_1") (pintype "input"))
      (node (ref "C29") (pin "1") (pinfunction "1_1") (pintype "input"))
      (node (ref "U3") (pin "18") (pinfunction "LDOO_18") (pintype "input"))
    )
    (net (code "24") (name "Net-(U3-LRCK)") (class "Default")
      (node (ref "R15") (pin "2") (pinfunction "2_2") (pintype "input"))
      (node (ref "U3") (pin "15") (pinfunction "LRCK_15") (pintype "input"))
    )
    (net (code "25") (name "Net-(U3-OUTL)") (class "Default")
      (node (ref "R12") (pin "1") (pinfunction "1_1") (pintype "input"))
      (node (ref "U3") (pin "6") (pinfunction "OUTL_6") (pintype "input"))
    )
    (net (code "26") (name "Net-(U3-OUTR)") (class "Default")
      (node (ref "R11") (pin "1") (pinfunction "1_1") (pintype "input"))
      (node (ref "U3") (pin "7") (pinfunction "OUTR_7") (pintype "input"))
    )
    (net (code "27") (name "Net-(U3-VNEG)") (class "Default")
      (node (ref "C10") (pin "2") (pinfunction "2_2") (pintype "input"))
      (node (ref "U3") (pin "5") (pinfunction "VNEG_5") (pintype "input"))
    )
    (net (code "28") (name "Net-(U6-CPN)") (class "Default")
      (node (ref "C17") (pin "1") (pinfunction "1_1") (pintype "input"))
      (node (ref "U6") (pin "9") (pinfunction "CPN_9") (pintype "input"))
    )
    (net (code "29") (name "Net-(U6-CPP)") (class "Default")
      (node (ref "C17") (pin "2") (pinfunction "2_2") (pintype "input"))
      (node (ref "U6") (pin "11") (pinfunction "CPP_11") (pintype "input"))
    )
    (net (code "30") (name "Net-(U6-HPVDD)") (class "Default")
      (node (ref "C14") (pin "2") (pinfunction "2_2") (pintype "input"))
      (node (ref "U6") (pin "12") (pinfunction "HPVDD_12") (pintype "input"))
    )
    (net (code "31") (name "Net-(U6-HPVSS)") (class "Default")
      (node (ref "C16") (pin "1") (pinfunction "1_1") (pintype "input"))
      (node (ref "U6") (pin "8") (pinfunction "HPVSS_8") (pintype "input"))
    )
    (net (code "32") (name "Net-(U6-INL-)") (class "Default")
      (node (ref "C12") (pin "1") (pinfunction "1_1") (pintype "input"))
      (node (ref "R11") (pin "2") (pinfunction "2_2") (pintype "input"))
      (node (ref "U6") (pin "1") (pinfunction "INL-_1") (pintype "input"))
    )
    (net (code "33") (name "Net-(U6-INR-)") (class "Default")
      (node (ref "C11") (pin "1") (pinfunction "1_1") (pintype "input"))
      (node (ref "R12") (pin "2") (pinfunction "2_2") (pintype "input"))
      (node (ref "U6") (pin "4") (pinfunction "INR-_4") (pintype "input"))
    )
    (net (code "34") (name "Net-(U6-OUTL)") (class "Default")
      (node (ref "CN1") (pin "2") (pinfunction "2_2") (pintype "unspecified"))
      (node (ref "U6") (pin "16") (pinfunction "OUTL_16") (pintype "input"))
    )
    (net (code "35") (name "Net-(U6-OUTR)") (class "Default")
      (node (ref "CN1") (pin "3") (pinfunction "3_3") (pintype "unspecified"))
      (node (ref "U6") (pin "5") (pinfunction "OUTR_5") (pintype "input"))
    )
    (net (code "36") (name "Net-(USBC1-CC1)") (class "Default")
      (node (ref "R8") (pin "1") (pinfunction "1_1") (pintype "input"))
      (node (ref "USBC1") (pin "A5") (pinfunction "CC1_A5") (pintype "unspecified"))
    )
    (net (code "37") (name "Net-(USBC1-CC2)") (class "Default")
      (node (ref "R7") (pin "1") (pinfunction "1_1") (pintype "input"))
      (node (ref "USBC1") (pin "B5") (pinfunction "CC2_B5") (pintype "unspecified"))
    )
    (net (code "38") (name "Net-(USBC1-DN1)") (class "Default")
      (node (ref "C3") (pin "1") (pinfunction "1_1") (pintype "input"))
      (node (ref "D4") (pin "2") (pinfunction "2_2") (pintype "unspecified"))
      (node (ref "R6") (pin "2") (pinfunction "2_2") (pintype "input"))
      (node (ref "USBC1") (pin "A7") (pinfunction "DN1_A7") (pintype "unspecified"))
      (node (ref "USBC1") (pin "B7") (pinfunction "DN2_B7") (pintype "unspecified"))
    )
    (net (code "39") (name "Net-(USBC1-DP1)") (class "Default")
      (node (ref "C4") (pin "1") (pinfunction "1_1") (pintype "input"))
      (node (ref "D5") (pin "2") (pinfunction "2_2") (pintype "unspecified"))
      (node (ref "R5") (pin "2") (pinfunction "2_2") (pintype "input"))
      (node (ref "USBC1") (pin "A6") (pinfunction "DP1_A6") (pintype "unspecified"))
      (node (ref "USBC1") (pin "B6") (pinfunction "DP2_B6") (pintype "unspecified"))
    )
    (net (code "40") (name "unconnected-(CN1-Pad4)") (class "Default")
      (node (ref "CN1") (pin "4") (pinfunction "4_4") (pintype "unspecified+no_connect"))
    )
    (net (code "41") (name "unconnected-(LDO1-NC-Pad4)") (class "Default")
      (node (ref "LDO1") (pin "4") (pinfunction "NC_4") (pintype "unspecified+no_connect"))
    )
    (net (code "42") (name "unconnected-(LDO2-NC-Pad4)") (class "Default")
      (node (ref "LDO2") (pin "4") (pinfunction "NC_4") (pintype "unspecified+no_connect"))
    )
    (net (code "43") (name "unconnected-(LDO3-NC-Pad4)") (class "Default")
      (node (ref "LDO3") (pin "4") (pinfunction "NC_4") (pintype "unspecified+no_connect"))
    )
    (net (code "44") (name "unconnected-(U2-GPIO8-Pad14)") (class "Default")
      (node (ref "U2") (pin "14") (pinfunction "GPIO8_14") (pintype "unspecified+no_connect"))
    )
    (net (code "45") (name "unconnected-(U2-LNA_IN-Pad1)") (class "Default")
      (node (ref "U2") (pin "1") (pinfunction "LNA_IN_1") (pintype "unspecified+no_connect"))
    )
    (net (code "46") (name "unconnected-(U2-MTCK-Pad12)") (class "Default")
      (node (ref "U2") (pin "12") (pinfunction "MTCK_12") (pintype "unspecified+no_connect"))
    )
    (net (code "47") (name "unconnected-(U2-MTDI-Pad10)") (class "Default")
      (node (ref "U2") (pin "10") (pinfunction "MTDI_10") (pintype "unspecified+no_connect"))
    )
    (net (code "48") (name "unconnected-(U2-MTDO-Pad13)") (class "Default")
      (node (ref "U2") (pin "13") (pinfunction "MTDO_13") (pintype "unspecified+no_connect"))
    )
    (net (code "49") (name "unconnected-(U2-MTMS-Pad9)") (class "Default")
      (node (ref "U2") (pin "9") (pinfunction "MTMS_9") (pintype "unspecified+no_connect"))
    )
    (net (code "50") (name "unconnected-(U2-SPICLK-Pad22)") (class "Default")
      (node (ref "U2") (pin "22") (pinfunction "SPICLK_22") (pintype "unspecified+no_connect"))
    )
    (net (code "51") (name "unconnected-(U2-SPICS0-Pad21)") (class "Default")
      (node (ref "U2") (pin "21") (pinfunction "SPICS0_21") (pintype "unspecified+no_connect"))
    )
    (net (code "52") (name "unconnected-(U2-SPID-Pad23)") (class "Default")
      (node (ref "U2") (pin "23") (pinfunction "SPID_23") (pintype "unspecified+no_connect"))
    )
    (net (code "53") (name "unconnected-(U2-SPIHD-Pad19)") (class "Default")
      (node (ref "U2") (pin "19") (pinfunction "SPIHD_19") (pintype "unspecified+no_connect"))
    )
    (net (code "54") (name "unconnected-(U2-SPIQ-Pad24)") (class "Default")
      (node (ref "U2") (pin "24") (pinfunction "SPIQ_24") (pintype "unspecified+no_connect"))
    )
    (net (code "55") (name "unconnected-(U2-SPIWP-Pad20)") (class "Default")
      (node (ref "U2") (pin "20") (pinfunction "SPIWP_20") (pintype "unspecified+no_connect"))
    )
    (net (code "56") (name "unconnected-(U2-U0RXD-Pad27)") (class "Default")
      (node (ref "U2") (pin "27") (pinfunction "U0RXD_27") (pintype "unspecified+no_connect"))
    )
    (net (code "57") (name "unconnected-(U2-U0TXD-Pad28)") (class "Default")
      (node (ref "U2") (pin "28") (pinfunction "U0TXD_28") (pintype "unspecified+no_connect"))
    )
    (net (code "58") (name "unconnected-(U2-VDD3P3-Pad2)") (class "Default")
      (node (ref "U2") (pin "2") (pinfunction "VDD3P3_2") (pintype "unspecified+no_connect"))
    )
    (net (code "59") (name "unconnected-(U2-VDD3P3-Pad3)") (class "Default")
      (node (ref "U2") (pin "3") (pinfunction "VDD3P3_3") (pintype "unspecified+no_connect"))
    )
    (net (code "60") (name "unconnected-(U2-VDD3P3_RTC-Pad11)") (class "Default")
      (node (ref "U2") (pin "11") (pinfunction "VDD3P3_RTC_11") (pintype "unspecified+no_connect"))
    )
    (net (code "61") (name "unconnected-(U2-VDD_SPI-Pad18)") (class "Default")
      (node (ref "U2") (pin "18") (pinfunction "VDD_SPI_18") (pintype "unspecified+no_connect"))
    )
    (net (code "62") (name "unconnected-(U2-XTAL_N-Pad29)") (class "Default")
      (node (ref "U2") (pin "29") (pinfunction "XTAL_N_29") (pintype "unspecified+no_connect"))
    )
    (net (code "63") (name "unconnected-(U2-XTAL_P-Pad30)") (class "Default")
      (node (ref "U2") (pin "30") (pinfunction "XTAL_P_30") (pintype "unspecified+no_connect"))
    )
    (net (code "64") (name "unconnected-(U3-XSMT-Pad17)") (class "Default")
      (node (ref "U3") (pin "17") (pinfunction "XSMT_17") (pintype "input+no_connect"))
    )
    (net (code "65") (name "unconnected-(USBC1-SBU1-PadA8)") (class "Default")
      (node (ref "USBC1") (pin "A8") (pinfunction "SBU1_A8") (pintype "unspecified+no_connect"))
    )
    (net (code "66") (name "unconnected-(USBC1-SBU2-PadB8)") (class "Default")
      (node (ref "USBC1") (pin "B8") (pinfunction "SBU2_B8") (pintype "unspecified+no_connect"))
    )
  )
)
